# MAIN_STM32L476RGT6.net
KiCad netlist of a schematic drawn in Altium Designer
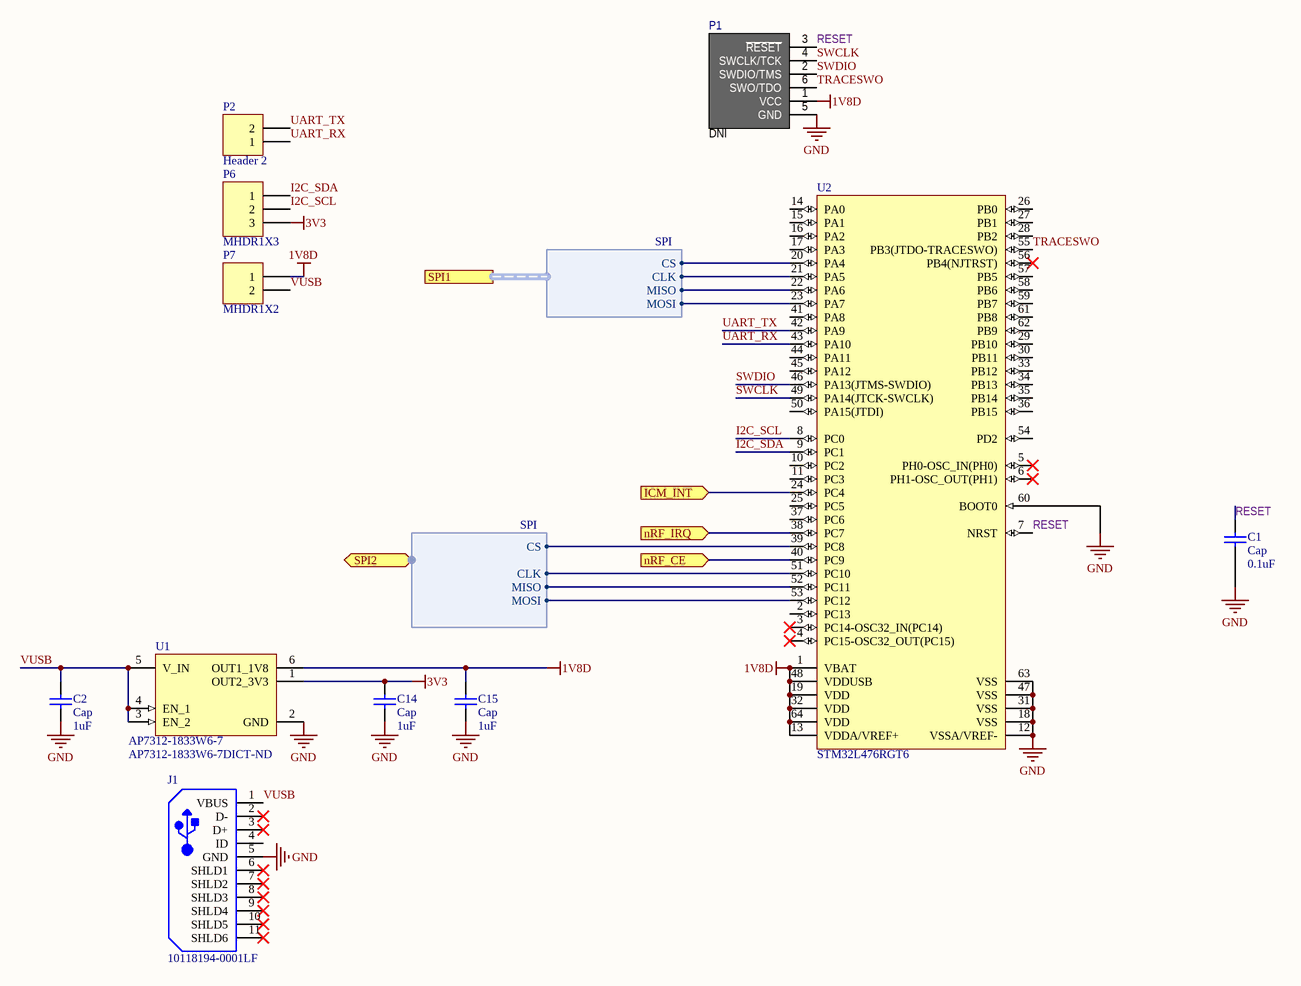
[diagram p0: MAIN_STM32L476RGT6.SchDoc]

(export (version "E")
  (design (tool "Eeschema 10.0.6"))
  (components
    (comp (ref "C1")
      (value "Cap")
      (footprint "CAPC1005N")
      (description "Capacitor")
      (fields (field (name "ALTIUM_VALUE") "0.1uF") (field (name "PUBLISHER") "Altium Limited"))
      (libsource (lib "Miscellaneous Devices") (part "Cap"))
    )
    (comp (ref "C2")
      (value "Cap")
      (footprint "CAPC1005N")
      (description "Capacitor")
      (fields (field (name "ALTIUM_VALUE") "1uF") (field (name "PUBLISHER") "Altium Limited"))
      (libsource (lib "Miscellaneous Devices") (part "Cap"))
    )
    (comp (ref "C14")
      (value "Cap")
      (footprint "CAPC1005N")
      (description "Capacitor")
      (fields (field (name "ALTIUM_VALUE") "1uF") (field (name "PUBLISHER") "Altium Limited"))
      (libsource (lib "Miscellaneous Devices") (part "Cap"))
    )
    (comp (ref "C15")
      (value "Cap")
      (footprint "CAPC1005N")
      (description "Capacitor")
      (fields (field (name "ALTIUM_VALUE") "1uF") (field (name "PUBLISHER") "Altium Limited"))
      (libsource (lib "Miscellaneous Devices") (part "Cap"))
    )
    (comp (ref "J1")
      (value "10118194-0001LF")
      (footprint "FCI-10118194-0001LF-5_V")
      (description "Micro USB B Type Receptacle, 1.8 A, -55 to 85 degC, 5-Pin SMD, RoHS, Tape and Reel")
      (fields (field (name "MANUFACTURER") "Amphenol FCI"))
      (libsource (lib "Altium Content Vault") (part "USB-5-6SHLD"))
    )
    (comp (ref "P1") (value "DNI") (footprint "TC2030") (libsource (lib "TagConnect") (part "TC2030-CTX")))
    (comp (ref "P2")
      (value "Header 2")
      (footprint "HDR1X2-PINS")
      (description "Header, 2-Pin")
      (fields (field (name "PUBLISHER") "Altium Limited"))
      (libsource (lib "Miscellaneous Connectors") (part "Header 2"))
    )
    (comp (ref "P6")
      (value "MHDR1X3")
      (footprint "MHDR1X3")
      (description "Header, 3-Pin")
      (fields (field (name "PUBLISHER") "Altium Limited"))
      (libsource (lib "Miscellaneous Connectors") (part "MHDR1X3"))
    )
    (comp (ref "P7")
      (value "MHDR1X2")
      (footprint "MHDR1X2")
      (description "Header, 2-Pin")
      (fields (field (name "PUBLISHER") "Altium Limited"))
      (libsource (lib "Miscellaneous Connectors") (part "MHDR1X2"))
    )
    (comp (ref "U1")
      (value "AP7312-1833W6-7")
      (footprint "SOT95P285X145-6N")
      (description "IC REG LINEAR 1.8V/3.3V SOT26")
      (fields (field (name "SUPPLIER PART NUMBER 1") "AP7312-1833W6-7DICT-ND"))
      (libsource (lib "Schlib1") (part "AP7312-1833W6-7"))
    )
    (comp (ref "U2")
      (value "STM32L476RGT6")
      (footprint "STM-LQFP64_N")
      (fields (field (name "MANUFACTURER") "STMicroelectronics"))
      (libsource (lib "Altium Content Vault") (part "MC-ARM-STM32L4X6-LQFP64"))
    )
  )
  (nets
    (net (code "2") (name "/I2C_SCL") (class "Default")
      (node (ref "P6") (pin "2") (pinfunction "2_2") (pintype "passive"))
      (node (ref "U2") (pin "8") (pinfunction "PC0_8") (pintype "bidirectional"))
    )
    (net (code "3") (name "/I2C_SDA") (class "Default")
      (node (ref "P6") (pin "1") (pinfunction "1_1") (pintype "passive"))
      (node (ref "U2") (pin "9") (pinfunction "PC1_9") (pintype "bidirectional"))
    )
    (net (code "4") (name "/ICM_INT") (class "Default")
      (node (ref "U2") (pin "24") (pinfunction "PC4_24") (pintype "bidirectional"))
    )
    (net (code "5") (name "/RESET") (class "Default")
      (node (ref "C1") (pin "2") (pinfunction "2_2") (pintype "passive"))
      (node (ref "P1") (pin "3") (pinfunction "~{RESET}_3") (pintype "passive"))
      (node (ref "U2") (pin "7") (pinfunction "NRST_7") (pintype "bidirectional"))
    )
    (net (code "6") (name "/SWCLK") (class "Default")
      (node (ref "P1") (pin "4") (pinfunction "SWCLK/TCK_4") (pintype "passive"))
      (node (ref "U2") (pin "49") (pinfunction "PA14(JTCK-SWCLK)_49") (pintype "bidirectional"))
    )
    (net (code "7") (name "/SWDIO") (class "Default")
      (node (ref "P1") (pin "2") (pinfunction "SWDIO/TMS_2") (pintype "passive"))
      (node (ref "U2") (pin "46") (pinfunction "PA13(JTMS-SWDIO)_46") (pintype "bidirectional"))
    )
    (net (code "8") (name "/TRACESWO") (class "Default")
      (node (ref "P1") (pin "6") (pinfunction "SWO/TDO_6") (pintype "passive"))
      (node (ref "U2") (pin "55") (pinfunction "PB3(JTDO-TRACESWO)_55") (pintype "bidirectional"))
    )
    (net (code "9") (name "/UART_RX") (class "Default")
      (node (ref "P2") (pin "1") (pinfunction "1_1") (pintype "passive"))
      (node (ref "U2") (pin "43") (pinfunction "PA10_43") (pintype "bidirectional"))
    )
    (net (code "10") (name "/UART_TX") (class "Default")
      (node (ref "P2") (pin "2") (pinfunction "2_2") (pintype "passive"))
      (node (ref "U2") (pin "42") (pinfunction "PA9_42") (pintype "bidirectional"))
    )
    (net (code "11") (name "/VUSB") (class "Default")
      (node (ref "C2") (pin "2") (pinfunction "2_2") (pintype "passive"))
      (node (ref "J1") (pin "1") (pinfunction "VBUS_1") (pintype "passive"))
      (node (ref "P7") (pin "2") (pinfunction "2_2") (pintype "passive"))
      (node (ref "U1") (pin "3") (pinfunction "EN_2_3") (pintype "input"))
      (node (ref "U1") (pin "4") (pinfunction "EN_1_4") (pintype "input"))
      (node (ref "U1") (pin "5") (pinfunction "V_IN_5") (pintype "power_in"))
    )
    (net (code "12") (name "/nRF_CE") (class "Default")
      (node (ref "U2") (pin "40") (pinfunction "PC9_40") (pintype "bidirectional"))
    )
    (net (code "13") (name "/nRF_IRQ") (class "Default")
      (node (ref "U2") (pin "38") (pinfunction "PC7_38") (pintype "bidirectional"))
    )
    (net (code "15") (name "1V8D") (class "Default")
      (node (ref "C15") (pin "2") (pinfunction "2_2") (pintype "passive"))
      (node (ref "P1") (pin "1") (pinfunction "VCC_1") (pintype "passive"))
      (node (ref "P7") (pin "1") (pinfunction "1_1") (pintype "passive"))
      (node (ref "U1") (pin "6") (pinfunction "OUT1_1V8_6") (pintype "power_in"))
      (node (ref "U2") (pin "1") (pinfunction "VBAT_1") (pintype "power_in"))
      (node (ref "U2") (pin "13") (pinfunction "VDDA/VREF+_13") (pintype "power_in"))
      (node (ref "U2") (pin "19") (pinfunction "VDD_19") (pintype "power_in"))
      (node (ref "U2") (pin "32") (pinfunction "VDD_32") (pintype "power_in"))
      (node (ref "U2") (pin "48") (pinfunction "VDDUSB_48") (pintype "power_in"))
      (node (ref "U2") (pin "64") (pinfunction "VDD_64") (pintype "power_in"))
    )
    (net (code "16") (name "3V3") (class "Default")
      (node (ref "C14") (pin "2") (pinfunction "2_2") (pintype "passive"))
      (node (ref "P6") (pin "3") (pinfunction "3_3") (pintype "passive"))
      (node (ref "U1") (pin "1") (pinfunction "OUT2_3V3_1") (pintype "power_in"))
    )
    (net (code "17") (name "GND") (class "Default")
      (node (ref "C1") (pin "1") (pinfunction "1_1") (pintype "passive"))
      (node (ref "C14") (pin "1") (pinfunction "1_1") (pintype "passive"))
      (node (ref "C15") (pin "1") (pinfunction "1_1") (pintype "passive"))
      (node (ref "C2") (pin "1") (pinfunction "1_1") (pintype "passive"))
      (node (ref "J1") (pin "5") (pinfunction "GND_5") (pintype "passive"))
      (node (ref "P1") (pin "5") (pinfunction "GND_5") (pintype "passive"))
      (node (ref "U1") (pin "2") (pinfunction "GND_2") (pintype "power_in"))
      (node (ref "U2") (pin "12") (pinfunction "VSSA/VREF-_12") (pintype "power_in"))
      (node (ref "U2") (pin "18") (pinfunction "VSS_18") (pintype "power_in"))
      (node (ref "U2") (pin "31") (pinfunction "VSS_31") (pintype "power_in"))
      (node (ref "U2") (pin "47") (pinfunction "VSS_47") (pintype "power_in"))
      (node (ref "U2") (pin "60") (pinfunction "BOOT0_60") (pintype "input"))
      (node (ref "U2") (pin "63") (pinfunction "VSS_63") (pintype "power_in"))
    )
    (net (code "18") (name "unconnected-(J1-D+-Pad3)") (class "Default")
      (node (ref "J1") (pin "3") (pinfunction "D+_3") (pintype "passive+no_connect"))
    )
    (net (code "19") (name "unconnected-(J1-D--Pad2)") (class "Default")
      (node (ref "J1") (pin "2") (pinfunction "D-_2") (pintype "passive+no_connect"))
    )
    (net (code "20") (name "unconnected-(J1-ID-Pad4)") (class "Default")
      (node (ref "J1") (pin "4") (pinfunction "ID_4") (pintype "passive"))
    )
    (net (code "21") (name "unconnected-(J1-SHLD1-Pad6)") (class "Default")
      (node (ref "J1") (pin "6") (pinfunction "SHLD1_6") (pintype "passive+no_connect"))
    )
    (net (code "22") (name "unconnected-(J1-SHLD2-Pad7)") (class "Default")
      (node (ref "J1") (pin "7") (pinfunction "SHLD2_7") (pintype "passive+no_connect"))
    )
    (net (code "23") (name "unconnected-(J1-SHLD3-Pad8)") (class "Default")
      (node (ref "J1") (pin "8") (pinfunction "SHLD3_8") (pintype "passive+no_connect"))
    )
    (net (code "24") (name "unconnected-(J1-SHLD4-Pad9)") (class "Default")
      (node (ref "J1") (pin "9") (pinfunction "SHLD4_9") (pintype "passive+no_connect"))
    )
    (net (code "25") (name "unconnected-(J1-SHLD5-Pad10)") (class "Default")
      (node (ref "J1") (pin "10") (pinfunction "SHLD5_10") (pintype "passive+no_connect"))
    )
    (net (code "26") (name "unconnected-(J1-SHLD6-Pad11)") (class "Default")
      (node (ref "J1") (pin "11") (pinfunction "SHLD6_11") (pintype "passive+no_connect"))
    )
    (net (code "27") (name "unconnected-(U2-PA0-Pad14)") (class "Default")
      (node (ref "U2") (pin "14") (pinfunction "PA0_14") (pintype "bidirectional"))
    )
    (net (code "28") (name "unconnected-(U2-PA1-Pad15)") (class "Default")
      (node (ref "U2") (pin "15") (pinfunction "PA1_15") (pintype "bidirectional"))
    )
    (net (code "29") (name "unconnected-(U2-PA2-Pad16)") (class "Default")
      (node (ref "U2") (pin "16") (pinfunction "PA2_16") (pintype "bidirectional"))
    )
    (net (code "30") (name "unconnected-(U2-PA3-Pad17)") (class "Default")
      (node (ref "U2") (pin "17") (pinfunction "PA3_17") (pintype "bidirectional"))
    )
    (net (code "31") (name "unconnected-(U2-PA4-Pad20)") (class "Default")
      (node (ref "U2") (pin "20") (pinfunction "PA4_20") (pintype "bidirectional"))
    )
    (net (code "32") (name "unconnected-(U2-PA5-Pad21)") (class "Default")
      (node (ref "U2") (pin "21") (pinfunction "PA5_21") (pintype "bidirectional"))
    )
    (net (code "33") (name "unconnected-(U2-PA6-Pad22)") (class "Default")
      (node (ref "U2") (pin "22") (pinfunction "PA6_22") (pintype "bidirectional"))
    )
    (net (code "34") (name "unconnected-(U2-PA7-Pad23)") (class "Default")
      (node (ref "U2") (pin "23") (pinfunction "PA7_23") (pintype "bidirectional"))
    )
    (net (code "35") (name "unconnected-(U2-PA8-Pad41)") (class "Default")
      (node (ref "U2") (pin "41") (pinfunction "PA8_41") (pintype "bidirectional"))
    )
    (net (code "36") (name "unconnected-(U2-PA11-Pad44)") (class "Default")
      (node (ref "U2") (pin "44") (pinfunction "PA11_44") (pintype "bidirectional"))
    )
    (net (code "37") (name "unconnected-(U2-PA12-Pad45)") (class "Default")
      (node (ref "U2") (pin "45") (pinfunction "PA12_45") (pintype "bidirectional"))
    )
    (net (code "38") (name "unconnected-(U2-PA15(JTDI)-Pad50)") (class "Default")
      (node (ref "U2") (pin "50") (pinfunction "PA15(JTDI)_50") (pintype "bidirectional"))
    )
    (net (code "39") (name "unconnected-(U2-PB0-Pad26)") (class "Default")
      (node (ref "U2") (pin "26") (pinfunction "PB0_26") (pintype "bidirectional"))
    )
    (net (code "40") (name "unconnected-(U2-PB1-Pad27)") (class "Default")
      (node (ref "U2") (pin "27") (pinfunction "PB1_27") (pintype "bidirectional"))
    )
    (net (code "41") (name "unconnected-(U2-PB2-Pad28)") (class "Default")
      (node (ref "U2") (pin "28") (pinfunction "PB2_28") (pintype "bidirectional"))
    )
    (net (code "42") (name "unconnected-(U2-PB4(NJTRST)-Pad56)") (class "Default")
      (node (ref "U2") (pin "56") (pinfunction "PB4(NJTRST)_56") (pintype "bidirectional+no_connect"))
    )
    (net (code "43") (name "unconnected-(U2-PB5-Pad57)") (class "Default")
      (node (ref "U2") (pin "57") (pinfunction "PB5_57") (pintype "bidirectional"))
    )
    (net (code "44") (name "unconnected-(U2-PB6-Pad58)") (class "Default")
      (node (ref "U2") (pin "58") (pinfunction "PB6_58") (pintype "bidirectional"))
    )
    (net (code "45") (name "unconnected-(U2-PB7-Pad59)") (class "Default")
      (node (ref "U2") (pin "59") (pinfunction "PB7_59") (pintype "bidirectional"))
    )
    (net (code "46") (name "unconnected-(U2-PB8-Pad61)") (class "Default")
      (node (ref "U2") (pin "61") (pinfunction "PB8_61") (pintype "bidirectional"))
    )
    (net (code "47") (name "unconnected-(U2-PB9-Pad62)") (class "Default")
      (node (ref "U2") (pin "62") (pinfunction "PB9_62") (pintype "bidirectional"))
    )
    (net (code "48") (name "unconnected-(U2-PB10-Pad29)") (class "Default")
      (node (ref "U2") (pin "29") (pinfunction "PB10_29") (pintype "bidirectional"))
    )
    (net (code "49") (name "unconnected-(U2-PB11-Pad30)") (class "Default")
      (node (ref "U2") (pin "30") (pinfunction "PB11_30") (pintype "bidirectional"))
    )
    (net (code "50") (name "unconnected-(U2-PB12-Pad33)") (class "Default")
      (node (ref "U2") (pin "33") (pinfunction "PB12_33") (pintype "bidirectional"))
    )
    (net (code "51") (name "unconnected-(U2-PB13-Pad34)") (class "Default")
      (node (ref "U2") (pin "34") (pinfunction "PB13_34") (pintype "bidirectional"))
    )
    (net (code "52") (name "unconnected-(U2-PB14-Pad35)") (class "Default")
      (node (ref "U2") (pin "35") (pinfunction "PB14_35") (pintype "bidirectional"))
    )
    (net (code "53") (name "unconnected-(U2-PB15-Pad36)") (class "Default")
      (node (ref "U2") (pin "36") (pinfunction "PB15_36") (pintype "bidirectional"))
    )
    (net (code "54") (name "unconnected-(U2-PC2-Pad10)") (class "Default")
      (node (ref "U2") (pin "10") (pinfunction "PC2_10") (pintype "bidirectional"))
    )
    (net (code "55") (name "unconnected-(U2-PC3-Pad11)") (class "Default")
      (node (ref "U2") (pin "11") (pinfunction "PC3_11") (pintype "bidirectional"))
    )
    (net (code "56") (name "unconnected-(U2-PC5-Pad25)") (class "Default")
      (node (ref "U2") (pin "25") (pinfunction "PC5_25") (pintype "bidirectional"))
    )
    (net (code "57") (name "unconnected-(U2-PC6-Pad37)") (class "Default")
      (node (ref "U2") (pin "37") (pinfunction "PC6_37") (pintype "bidirectional"))
    )
    (net (code "58") (name "unconnected-(U2-PC8-Pad39)") (class "Default")
      (node (ref "U2") (pin "39") (pinfunction "PC8_39") (pintype "bidirectional"))
    )
    (net (code "59") (name "unconnected-(U2-PC10-Pad51)") (class "Default")
      (node (ref "U2") (pin "51") (pinfunction "PC10_51") (pintype "bidirectional"))
    )
    (net (code "60") (name "unconnected-(U2-PC11-Pad52)") (class "Default")
      (node (ref "U2") (pin "52") (pinfunction "PC11_52") (pintype "bidirectional"))
    )
    (net (code "61") (name "unconnected-(U2-PC12-Pad53)") (class "Default")
      (node (ref "U2") (pin "53") (pinfunction "PC12_53") (pintype "bidirectional"))
    )
    (net (code "62") (name "unconnected-(U2-PC13-Pad2)") (class "Default")
      (node (ref "U2") (pin "2") (pinfunction "PC13_2") (pintype "bidirectional"))
    )
    (net (code "63") (name "unconnected-(U2-PC14-OSC32_IN(PC14)-Pad3)") (class "Default")
      (node (ref "U2") (pin "3") (pinfunction "PC14-OSC32_IN(PC14)_3") (pintype "bidirectional+no_connect"))
    )
    (net (code "64") (name "unconnected-(U2-PC15-OSC32_OUT(PC15)-Pad4)") (class "Default")
      (node (ref "U2") (pin "4") (pinfunction "PC15-OSC32_OUT(PC15)_4") (pintype "bidirectional+no_connect"))
    )
    (net (code "65") (name "unconnected-(U2-PD2-Pad54)") (class "Default")
      (node (ref "U2") (pin "54") (pinfunction "PD2_54") (pintype "bidirectional"))
    )
    (net (code "66") (name "unconnected-(U2-PH0-OSC_IN(PH0)-Pad5)") (class "Default")
      (node (ref "U2") (pin "5") (pinfunction "PH0-OSC_IN(PH0)_5") (pintype "bidirectional+no_connect"))
    )
    (net (code "67") (name "unconnected-(U2-PH1-OSC_OUT(PH1)-Pad6)") (class "Default")
      (node (ref "U2") (pin "6") (pinfunction "PH1-OSC_OUT(PH1)_6") (pintype "bidirectional+no_connect"))
    )
  )
)
